# LightSensorWiring.net
KiCad netlist of a schematic drawn in EAGLE
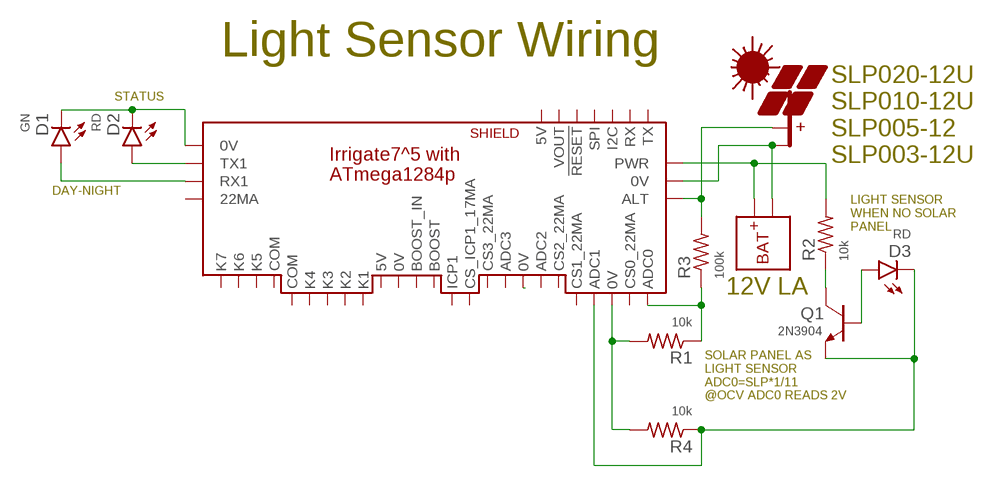
[diagram p0: schematic, sheet 1]

(export (version "E")
  (design (tool "Eeschema 10.0.6"))
  (components
    (comp (ref "D1")
      (value "GN")
      (footprint "eagle-import:LED5MM")
      (libsource (lib "eagle-import") (part "LED5MM"))
    )
    (comp (ref "D2")
      (value "RD")
      (footprint "eagle-import:LED5MM")
      (libsource (lib "eagle-import") (part "LED5MM"))
    )
    (comp (ref "D3")
      (value "RD")
      (footprint "eagle-import:LED5MM")
      (libsource (lib "eagle-import") (part "LED5MM"))
    )
    (comp (ref "PV4")
      (value "PV")
      (footprint "eagle-import:NA-30")
      (libsource (lib "eagle-import") (part "PV"))
    )
    (comp (ref "Q1")
      (value "2N3904")
      (footprint "eagle-import:SOT23")
      (libsource (lib "eagle-import") (part "NPNSOT23"))
    )
    (comp (ref "R1")
      (value "10k")
      (footprint "eagle-import:C0805(2012)")
      (libsource (lib "eagle-import") (part "R0805"))
    )
    (comp (ref "R2")
      (value "10k")
      (footprint "eagle-import:C0805(2012)")
      (libsource (lib "eagle-import") (part "R0805"))
    )
    (comp (ref "R3")
      (value "100k")
      (footprint "eagle-import:C0805(2012)")
      (libsource (lib "eagle-import") (part "R0805"))
    )
    (comp (ref "R4")
      (value "10k")
      (footprint "eagle-import:C0805(2012)")
      (libsource (lib "eagle-import") (part "R0805"))
    )
    (comp (ref "U$1")
      (value "IRRIGATE7")
      (footprint "eagle-import:WITH_RPU_NAMES")
      (libsource (lib "eagle-import") (part "IRRIGATE7"))
    )
    (comp (ref "U$7")
      (value "BAT")
      (footprint "eagle-import:NA-30")
      (libsource (lib "eagle-import") (part "BAT"))
    )
  )
  (nets
    (net (code "1") (name "Net-(D1-PadK)") (class "Default")
      (node (ref "D1") (pin "K") (pinfunction "K_K") (pintype "passive"))
      (node (ref "D2") (pin "K") (pinfunction "K_K") (pintype "passive"))
      (node (ref "U$1") (pin "17MA@ICP3") (pinfunction "0V_17MA@ICP3") (pintype "bidirectional"))
    )
    (net (code "2") (name "Net-(D3-PadA)") (class "Default")
      (node (ref "D3") (pin "A") (pinfunction "A_A") (pintype "passive"))
      (node (ref "Q1") (pin "B") (pinfunction "B_B") (pintype "passive"))
    )
    (net (code "3") (name "Net-(D3-PadK)") (class "Default")
      (node (ref "D3") (pin "K") (pinfunction "K_K") (pintype "passive"))
      (node (ref "Q1") (pin "E") (pinfunction "E_E") (pintype "passive"))
      (node (ref "R4") (pin "1") (pinfunction "1_1") (pintype "passive"))
      (node (ref "U$1") (pin "ADC1") (pinfunction "ADC1_ADC1") (pintype "bidirectional"))
    )
    (net (code "4") (name "Net-(PV4-+PV)") (class "Default")
      (node (ref "PV4") (pin "1") (pinfunction "+PV_1") (pintype "bidirectional"))
      (node (ref "R3") (pin "2") (pinfunction "2_2") (pintype "passive"))
      (node (ref "U$1") (pin "AUX") (pinfunction "ALT_AUX") (pintype "bidirectional"))
    )
    (net (code "5") (name "Net-(PV4--PV)") (class "Default")
      (node (ref "PV4") (pin "2") (pinfunction "-PV_2") (pintype "bidirectional"))
      (node (ref "U$1") (pin "0V@PWR") (pinfunction "0V_0V@PWR") (pintype "bidirectional"))
      (node (ref "U$7") (pin "2") (pinfunction "-BAT_2") (pintype "bidirectional"))
    )
    (net (code "6") (name "Net-(Q1-PadC)") (class "Default")
      (node (ref "Q1") (pin "C") (pinfunction "C_C") (pintype "passive"))
      (node (ref "R2") (pin "1") (pinfunction "1_1") (pintype "passive"))
    )
    (net (code "7") (name "Net-(R1-Pad1)") (class "Default")
      (node (ref "R1") (pin "1") (pinfunction "1_1") (pintype "passive"))
      (node (ref "R3") (pin "1") (pinfunction "1_1") (pintype "passive"))
      (node (ref "U$1") (pin "ADC0") (pinfunction "ADC0_ADC0") (pintype "bidirectional"))
    )
    (net (code "8") (name "Net-(R1-Pad2)") (class "Default")
      (node (ref "R1") (pin "2") (pinfunction "2_2") (pintype "passive"))
      (node (ref "R4") (pin "2") (pinfunction "2_2") (pintype "passive"))
      (node (ref "U$1") (pin "0V@ADC2") (pinfunction "0V_0V@ADC2") (pintype "bidirectional"))
    )
    (net (code "9") (name "Net-(U$1-RX1)") (class "Default")
      (node (ref "D1") (pin "A") (pinfunction "A_A") (pintype "passive"))
      (node (ref "U$1") (pin "DIO2") (pinfunction "RX1_DIO2") (pintype "bidirectional"))
    )
    (net (code "10") (name "Net-(U$1-TX1)") (class "Default")
      (node (ref "D2") (pin "A") (pinfunction "A_A") (pintype "passive"))
      (node (ref "U$1") (pin "DIO3") (pinfunction "TX1_DIO3") (pintype "bidirectional"))
    )
    (net (code "11") (name "Net-(U$7-+BAT)") (class "Default")
      (node (ref "R2") (pin "2") (pinfunction "2_2") (pintype "passive"))
      (node (ref "U$1") (pin "PWR") (pinfunction "PWR_PWR") (pintype "bidirectional"))
      (node (ref "U$7") (pin "1") (pinfunction "+BAT_1") (pintype "bidirectional"))
    )
    (net (code "12") (name "unconnected-(U$1-0V-PadICP3)") (class "Default")
      (node (ref "U$1") (pin "ICP3") (pinfunction "0V_ICP3") (pintype "bidirectional"))
    )
    (net (code "13") (name "unconnected-(U$1-5V-PadSHLD_5V)") (class "Default")
      (node (ref "U$1") (pin "SHLD_5V") (pinfunction "5V_SHLD_5V") (pintype "bidirectional"))
    )
    (net (code "14") (name "unconnected-(U$1-22MA-Pad22MA@DIO2)") (class "Default")
      (node (ref "U$1") (pin "22MA@DIO2") (pinfunction "22MA_22MA@DIO2") (pintype "bidirectional"))
    )
    (net (code "15") (name "unconnected-(U$1-ADC2-PadADC4)") (class "Default")
      (node (ref "U$1") (pin "ADC4") (pinfunction "ADC2_ADC4") (pintype "bidirectional"))
    )
    (net (code "16") (name "unconnected-(U$1-ADC3-PadADC5)") (class "Default")
      (node (ref "U$1") (pin "ADC5") (pinfunction "ADC3_ADC5") (pintype "bidirectional"))
    )
    (net (code "17") (name "unconnected-(U$1-COM-PadCOM@K4)") (class "Default")
      (node (ref "U$1") (pin "COM@K4") (pinfunction "COM_COM@K4") (pintype "bidirectional"))
    )
    (net (code "18") (name "unconnected-(U$1-COM-PadCOM@K5)") (class "Default")
      (node (ref "U$1") (pin "COM@K5") (pinfunction "COM_COM@K5") (pintype "bidirectional"))
    )
    (net (code "19") (name "unconnected-(U$1-CS0_22MA-Pad22MA@ADC0)") (class "Default")
      (node (ref "U$1") (pin "22MA@ADC0") (pinfunction "CS0_22MA_22MA@ADC0") (pintype "bidirectional"))
    )
    (net (code "20") (name "unconnected-(U$1-CS1_22MA-Pad22MA@ADC1)") (class "Default")
      (node (ref "U$1") (pin "22MA@ADC1") (pinfunction "CS1_22MA_22MA@ADC1") (pintype "bidirectional"))
    )
    (net (code "21") (name "unconnected-(U$1-CS2_22MA-Pad22MA@ADC4)") (class "Default")
      (node (ref "U$1") (pin "22MA@ADC4") (pinfunction "CS2_22MA_22MA@ADC4") (pintype "bidirectional"))
    )
    (net (code "22") (name "unconnected-(U$1-CS3_22MA-Pad22MA@ADC5)") (class "Default")
      (node (ref "U$1") (pin "22MA@ADC5") (pinfunction "CS3_22MA_22MA@ADC5") (pintype "bidirectional"))
    )
    (net (code "23") (name "unconnected-(U$1-CS_ICP1_17MA-Pad17MA@ICP1)") (class "Default")
      (node (ref "U$1") (pin "17MA@ICP1") (pinfunction "CS_ICP1_17MA_17MA@ICP1") (pintype "bidirectional"))
    )
    (net (code "24") (name "unconnected-(U$1-Pad0V)") (class "Default")
      (node (ref "U$1") (pin "0V") (pinfunction "0V_0V") (pintype "bidirectional"))
    )
    (net (code "25") (name "unconnected-(U$1-Pad5V)") (class "Default")
      (node (ref "U$1") (pin "5V") (pinfunction "5V_5V") (pintype "bidirectional"))
    )
    (net (code "26") (name "unconnected-(U$1-PadBOOST)") (class "Default")
      (node (ref "U$1") (pin "BOOST") (pinfunction "BOOST_BOOST") (pintype "bidirectional"))
    )
    (net (code "27") (name "unconnected-(U$1-PadBOOST_IN)") (class "Default")
      (node (ref "U$1") (pin "BOOST_IN") (pinfunction "BOOST_IN_BOOST_IN") (pintype "bidirectional"))
    )
    (net (code "28") (name "unconnected-(U$1-PadI2C)") (class "Default")
      (node (ref "U$1") (pin "I2C") (pinfunction "I2C_I2C") (pintype "bidirectional"))
    )
    (net (code "29") (name "unconnected-(U$1-PadICP1)") (class "Default")
      (node (ref "U$1") (pin "ICP1") (pinfunction "ICP1_ICP1") (pintype "bidirectional"))
    )
    (net (code "30") (name "unconnected-(U$1-PadK1)") (class "Default")
      (node (ref "U$1") (pin "K1") (pinfunction "K1_K1") (pintype "bidirectional"))
    )
    (net (code "31") (name "unconnected-(U$1-PadK2)") (class "Default")
      (node (ref "U$1") (pin "K2") (pinfunction "K2_K2") (pintype "bidirectional"))
    )
    (net (code "32") (name "unconnected-(U$1-PadK3)") (class "Default")
      (node (ref "U$1") (pin "K3") (pinfunction "K3_K3") (pintype "bidirectional"))
    )
    (net (code "33") (name "unconnected-(U$1-PadK4)") (class "Default")
      (node (ref "U$1") (pin "K4") (pinfunction "K4_K4") (pintype "bidirectional"))
    )
    (net (code "34") (name "unconnected-(U$1-PadK5)") (class "Default")
      (node (ref "U$1") (pin "K5") (pinfunction "K5_K5") (pintype "bidirectional"))
    )
    (net (code "35") (name "unconnected-(U$1-PadK6)") (class "Default")
      (node (ref "U$1") (pin "K6") (pinfunction "K6_K6") (pintype "bidirectional"))
    )
    (net (code "36") (name "unconnected-(U$1-PadK7)") (class "Default")
      (node (ref "U$1") (pin "K7") (pinfunction "K7_K7") (pintype "bidirectional"))
    )
    (net (code "37") (name "unconnected-(U$1-PadRX)") (class "Default")
      (node (ref "U$1") (pin "RX") (pinfunction "RX_RX") (pintype "bidirectional"))
    )
    (net (code "38") (name "unconnected-(U$1-PadSPI)") (class "Default")
      (node (ref "U$1") (pin "SPI") (pinfunction "SPI_SPI") (pintype "bidirectional"))
    )
    (net (code "39") (name "unconnected-(U$1-PadTX)") (class "Default")
      (node (ref "U$1") (pin "TX") (pinfunction "TX_TX") (pintype "bidirectional"))
    )
    (net (code "40") (name "unconnected-(U$1-VOUT-PadSHLD_VOUT)") (class "Default")
      (node (ref "U$1") (pin "SHLD_VOUT") (pinfunction "VOUT_SHLD_VOUT") (pintype "bidirectional"))
    )
    (net (code "41") (name "unconnected-(U$1-~{RESET}-Pad!RESET)") (class "Default")
      (node (ref "U$1") (pin "!RESET") (pinfunction "~{RESET}_!RESET") (pintype "bidirectional"))
    )
  )
)
